# esposi-base-v1.net
KiCad netlist of a schematic drawn in EAGLE
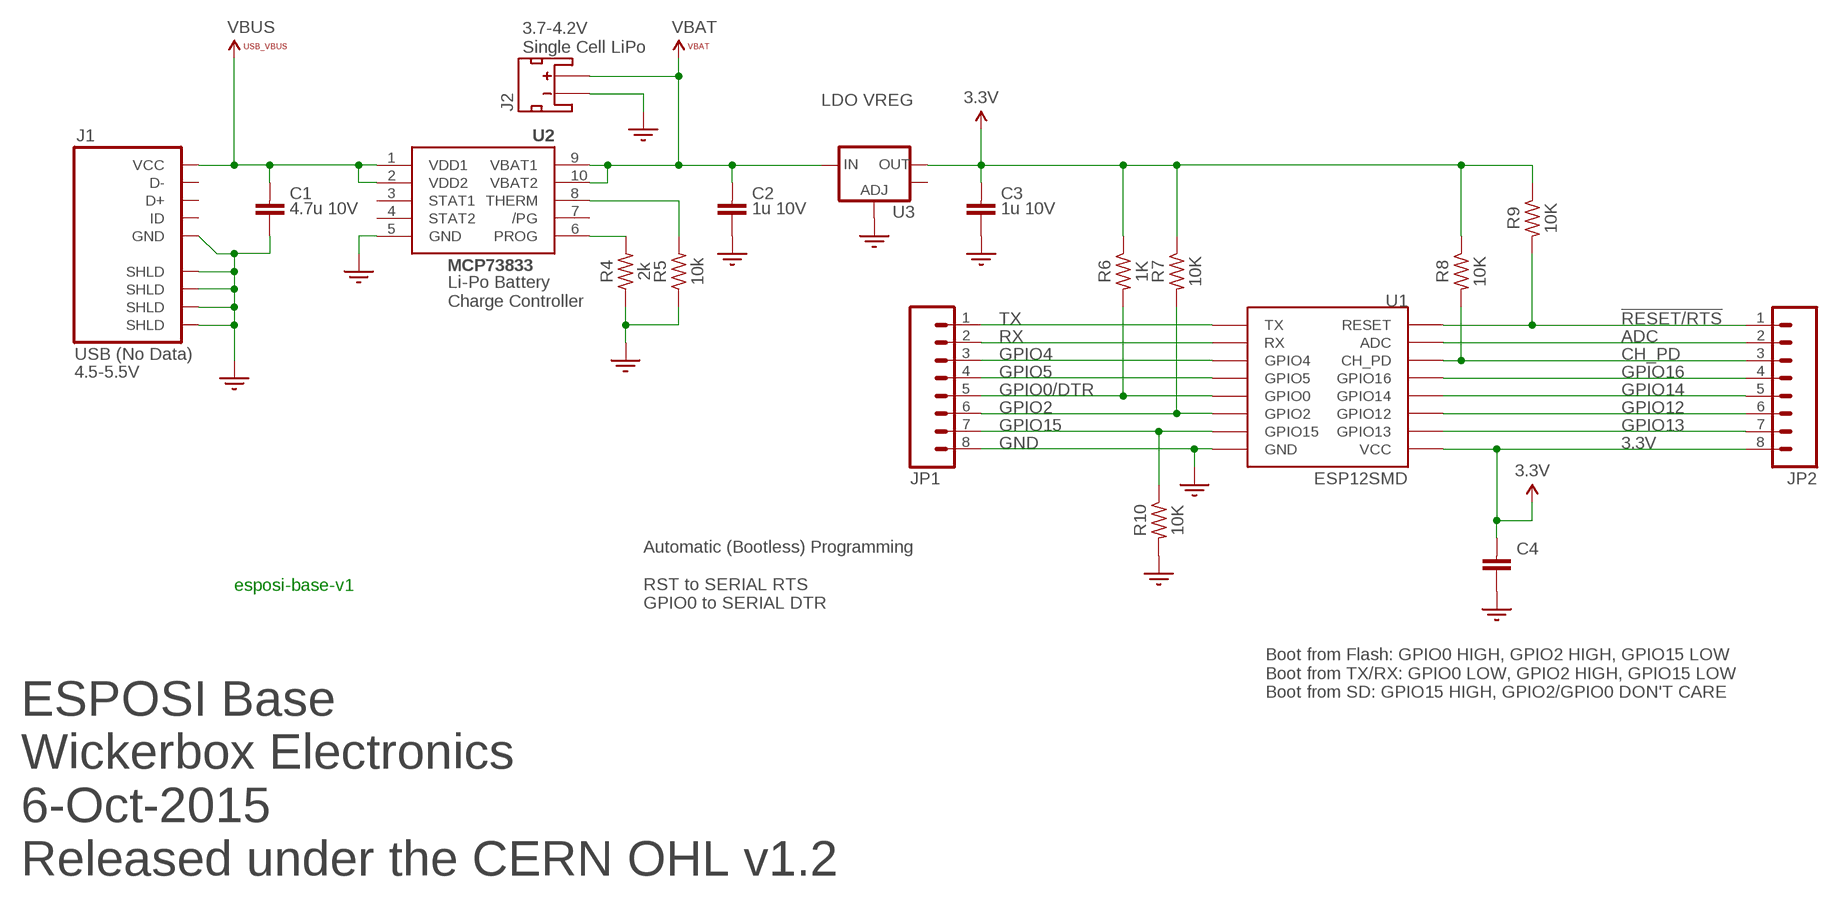
[diagram p0: schematic, sheet 1]

(export (version "E")
  (design (tool "Eeschema 10.0.6"))
  (components
    (comp (ref "C1")
      (value "4.7u 10V")
      (footprint "eagle-import:RLC-0805")
      (libsource (lib "eagle-import") (part "CAP-0805"))
    )
    (comp (ref "C2")
      (value "1u 10V")
      (footprint "eagle-import:RLC-0603")
      (libsource (lib "eagle-import") (part "CAP-0603"))
    )
    (comp (ref "C3")
      (value "1u 10V")
      (footprint "eagle-import:RLC-0603")
      (libsource (lib "eagle-import") (part "CAP-0603"))
    )
    (comp (ref "C4")
      (value "CAP-0402")
      (footprint "eagle-import:RLC-0402")
      (libsource (lib "eagle-import") (part "CAP-0402"))
    )
    (comp (ref "J1")
      (value "USB (No Data)")
      (footprint "eagle-import:ZX62D-B-5P8")
      (libsource (lib "eagle-import") (part "ZX62D-B-5P8"))
    )
    (comp (ref "J2")
      (value "JST_2MM_MALE")
      (footprint "eagle-import:JST-2-SMD")
      (libsource (lib "eagle-import") (part "JST_2MM_MALE"))
    )
    (comp (ref "JP1")
      (value "M08NO_SILK_FEMALE_PTH")
      (footprint "eagle-import:1X08_NO_SILK")
      (libsource (lib "eagle-import") (part "M08NO_SILK_FEMALE_PTH"))
    )
    (comp (ref "JP2")
      (value "M08NO_SILK_FEMALE_PTH")
      (footprint "eagle-import:1X08_NO_SILK")
      (libsource (lib "eagle-import") (part "M08NO_SILK_FEMALE_PTH"))
    )
    (comp (ref "R4")
      (value "2k")
      (footprint "eagle-import:RLC-0402")
      (libsource (lib "eagle-import") (part "RES-0402"))
    )
    (comp (ref "R5")
      (value "10k")
      (footprint "eagle-import:RLC-0402")
      (libsource (lib "eagle-import") (part "RES-0402"))
    )
    (comp (ref "R6")
      (value "1K")
      (footprint "eagle-import:RLC-0402")
      (libsource (lib "eagle-import") (part "RES-0402"))
    )
    (comp (ref "R7")
      (value "10K")
      (footprint "eagle-import:RLC-0402")
      (libsource (lib "eagle-import") (part "RES-0402"))
    )
    (comp (ref "R8")
      (value "10K")
      (footprint "eagle-import:RLC-0402")
      (libsource (lib "eagle-import") (part "RES-0402"))
    )
    (comp (ref "R9")
      (value "10K")
      (footprint "eagle-import:RLC-0402")
      (libsource (lib "eagle-import") (part "RES-0402"))
    )
    (comp (ref "R10")
      (value "10K")
      (footprint "eagle-import:RLC-0402")
      (libsource (lib "eagle-import") (part "RES-0402"))
    )
    (comp (ref "U1")
      (value "ESP12SMD")
      (footprint "eagle-import:ESP12_SMD")
      (libsource (lib "eagle-import") (part "ESP12SMD"))
    )
    (comp (ref "U2")
      (value "MCP73833-UN")
      (footprint "eagle-import:MSOP10")
      (libsource (lib "eagle-import") (part "MCP73833-UN"))
    )
    (comp (ref "U3")
      (value "V_REG_LM1117SOT223")
      (footprint "eagle-import:SOT223")
      (libsource (lib "eagle-import") (part "V_REG_LM1117SOT223"))
    )
  )
  (nets
    (net (code "1") (name "/ADC") (class "Default")
      (node (ref "JP2") (pin "2") (pinfunction "2_2") (pintype "passive"))
      (node (ref "U1") (pin "ADC") (pinfunction "ADC_ADC") (pintype "bidirectional"))
    )
    (net (code "2") (name "/CH_PD") (class "Default")
      (node (ref "JP2") (pin "3") (pinfunction "3_3") (pintype "passive"))
      (node (ref "R8") (pin "2") (pinfunction "2_2") (pintype "passive"))
      (node (ref "U1") (pin "CH_PD") (pinfunction "CH_PD_CH_PD") (pintype "bidirectional"))
    )
    (net (code "3") (name "/GPIO0{slash}DTR") (class "Default")
      (node (ref "JP1") (pin "5") (pinfunction "5_5") (pintype "passive"))
      (node (ref "R6") (pin "2") (pinfunction "2_2") (pintype "passive"))
      (node (ref "U1") (pin "GPIO0") (pinfunction "GPIO0_GPIO0") (pintype "bidirectional"))
    )
    (net (code "4") (name "/GPIO2") (class "Default")
      (node (ref "JP1") (pin "6") (pinfunction "6_6") (pintype "passive"))
      (node (ref "R7") (pin "2") (pinfunction "2_2") (pintype "passive"))
      (node (ref "U1") (pin "GPIO2") (pinfunction "GPIO2_GPIO2") (pintype "bidirectional"))
    )
    (net (code "5") (name "/GPIO4") (class "Default")
      (node (ref "JP1") (pin "3") (pinfunction "3_3") (pintype "passive"))
      (node (ref "U1") (pin "GPIO4") (pinfunction "GPIO4_GPIO4") (pintype "bidirectional"))
    )
    (net (code "6") (name "/GPIO5") (class "Default")
      (node (ref "JP1") (pin "4") (pinfunction "4_4") (pintype "passive"))
      (node (ref "U1") (pin "GPIO5") (pinfunction "GPIO5_GPIO5") (pintype "bidirectional"))
    )
    (net (code "7") (name "/GPIO12") (class "Default")
      (node (ref "JP2") (pin "6") (pinfunction "6_6") (pintype "passive"))
      (node (ref "U1") (pin "GPIO12") (pinfunction "GPIO12_GPIO12") (pintype "bidirectional"))
    )
    (net (code "8") (name "/GPIO13") (class "Default")
      (node (ref "JP2") (pin "7") (pinfunction "7_7") (pintype "passive"))
      (node (ref "U1") (pin "GPIO13") (pinfunction "GPIO13_GPIO13") (pintype "bidirectional"))
    )
    (net (code "9") (name "/GPIO14") (class "Default")
      (node (ref "JP2") (pin "5") (pinfunction "5_5") (pintype "passive"))
      (node (ref "U1") (pin "GPIO14") (pinfunction "GPIO14_GPIO14") (pintype "bidirectional"))
    )
    (net (code "10") (name "/GPIO15") (class "Default")
      (node (ref "JP1") (pin "7") (pinfunction "7_7") (pintype "passive"))
      (node (ref "R10") (pin "1") (pinfunction "1_1") (pintype "passive"))
      (node (ref "U1") (pin "GPIO15") (pinfunction "GPIO15_GPIO15") (pintype "bidirectional"))
    )
    (net (code "11") (name "/GPIO16") (class "Default")
      (node (ref "JP2") (pin "4") (pinfunction "4_4") (pintype "passive"))
      (node (ref "U1") (pin "GPIO16") (pinfunction "GPIO16_GPIO16") (pintype "bidirectional"))
    )
    (net (code "12") (name "/RX") (class "Default")
      (node (ref "JP1") (pin "2") (pinfunction "2_2") (pintype "passive"))
      (node (ref "U1") (pin "RX") (pinfunction "RX_RX") (pintype "bidirectional"))
    )
    (net (code "13") (name "/TX") (class "Default")
      (node (ref "JP1") (pin "1") (pinfunction "1_1") (pintype "passive"))
      (node (ref "U1") (pin "TX") (pinfunction "TX_TX") (pintype "bidirectional"))
    )
    (net (code "14") (name "/~{RESET{slash}RTS}") (class "Default")
      (node (ref "JP2") (pin "1") (pinfunction "1_1") (pintype "passive"))
      (node (ref "R9") (pin "2") (pinfunction "2_2") (pintype "passive"))
      (node (ref "U1") (pin "RESET") (pinfunction "RESET_RESET") (pintype "bidirectional"))
    )
    (net (code "15") (name "3.3V") (class "Default")
      (node (ref "C3") (pin "2") (pinfunction "1_2") (pintype "passive"))
      (node (ref "C4") (pin "1") (pinfunction "1_1") (pintype "passive"))
      (node (ref "JP2") (pin "8") (pinfunction "8_8") (pintype "passive"))
      (node (ref "R6") (pin "1") (pinfunction "1_1") (pintype "passive"))
      (node (ref "R7") (pin "1") (pinfunction "1_1") (pintype "passive"))
      (node (ref "R8") (pin "1") (pinfunction "1_1") (pintype "passive"))
      (node (ref "R9") (pin "1") (pinfunction "1_1") (pintype "passive"))
      (node (ref "U1") (pin "VCC") (pinfunction "VCC_VCC") (pintype "bidirectional"))
      (node (ref "U3") (pin "2") (pinfunction "OUT_2") (pintype "output"))
    )
    (net (code "16") (name "GND") (class "Default")
      (node (ref "C1") (pin "2") (pinfunction "2_2") (pintype "passive"))
      (node (ref "C2") (pin "1") (pinfunction "2_1") (pintype "passive"))
      (node (ref "C3") (pin "1") (pinfunction "2_1") (pintype "passive"))
      (node (ref "C4") (pin "2") (pinfunction "2_2") (pintype "passive"))
      (node (ref "J1") (pin "P$1") (pinfunction "SHLD_P$1") (pintype "power_in"))
      (node (ref "J1") (pin "P$2") (pinfunction "SHLD_P$2") (pintype "power_in"))
      (node (ref "J1") (pin "P$3") (pinfunction "SHLD_P$3") (pintype "power_in"))
      (node (ref "J1") (pin "P$4") (pinfunction "SHLD_P$4") (pintype "power_in"))
      (node (ref "J1") (pin "P5") (pinfunction "GND_P5") (pintype "power_in"))
      (node (ref "J2") (pin "1") (pinfunction "-_1") (pintype "bidirectional"))
      (node (ref "JP1") (pin "8") (pinfunction "8_8") (pintype "passive"))
      (node (ref "R10") (pin "2") (pinfunction "2_2") (pintype "passive"))
      (node (ref "R4") (pin "1") (pinfunction "1_1") (pintype "passive"))
      (node (ref "R5") (pin "1") (pinfunction "1_1") (pintype "passive"))
      (node (ref "U1") (pin "GND") (pinfunction "GND_GND") (pintype "bidirectional"))
      (node (ref "U2") (pin "5") (pinfunction "GND_5") (pintype "power_in"))
      (node (ref "U3") (pin "1") (pinfunction "ADJ_1") (pintype "input"))
    )
    (net (code "17") (name "Net-(U2-PROG)") (class "Default")
      (node (ref "R4") (pin "2") (pinfunction "2_2") (pintype "passive"))
      (node (ref "U2") (pin "6") (pinfunction "PROG_6") (pintype "input"))
    )
    (net (code "18") (name "Net-(U2-THERM)") (class "Default")
      (node (ref "R5") (pin "2") (pinfunction "2_2") (pintype "passive"))
      (node (ref "U2") (pin "8") (pinfunction "THERM_8") (pintype "bidirectional"))
    )
    (net (code "19") (name "VBAT") (class "Default")
      (node (ref "C2") (pin "2") (pinfunction "1_2") (pintype "passive"))
      (node (ref "J2") (pin "2") (pinfunction "+_2") (pintype "bidirectional"))
      (node (ref "U2") (pin "10") (pinfunction "VBAT2_10") (pintype "output"))
      (node (ref "U2") (pin "9") (pinfunction "VBAT1_9") (pintype "output"))
      (node (ref "U3") (pin "3") (pinfunction "IN_3") (pintype "input"))
    )
    (net (code "20") (name "VBUS") (class "Default")
      (node (ref "C1") (pin "1") (pinfunction "1_1") (pintype "passive"))
      (node (ref "J1") (pin "P1") (pinfunction "VCC_P1") (pintype "power_in"))
      (node (ref "U2") (pin "1") (pinfunction "VDD1_1") (pintype "power_in"))
      (node (ref "U2") (pin "2") (pinfunction "VDD2_2") (pintype "power_in"))
    )
    (net (code "21") (name "unconnected-(J1-D+-PadP3)") (class "Default")
      (node (ref "J1") (pin "P3") (pinfunction "D+_P3") (pintype "bidirectional"))
    )
    (net (code "22") (name "unconnected-(J1-D--PadP2)") (class "Default")
      (node (ref "J1") (pin "P2") (pinfunction "D-_P2") (pintype "bidirectional"))
    )
    (net (code "23") (name "unconnected-(J1-ID-PadP4)") (class "Default")
      (node (ref "J1") (pin "P4") (pinfunction "ID_P4") (pintype "bidirectional"))
    )
    (net (code "24") (name "unconnected-(J2-PAD1-PadNC1)") (class "Default")
      (node (ref "J2") (pin "NC1") (pinfunction "PAD1_NC1") (pintype "bidirectional"))
    )
    (net (code "25") (name "unconnected-(J2-PAD2-PadNC2)") (class "Default")
      (node (ref "J2") (pin "NC2") (pinfunction "PAD2_NC2") (pintype "bidirectional"))
    )
    (net (code "26") (name "unconnected-(U2-STAT1-Pad3)") (class "Default")
      (node (ref "U2") (pin "3") (pinfunction "STAT1_3") (pintype "passive"))
    )
    (net (code "27") (name "unconnected-(U2-STAT2-Pad4)") (class "Default")
      (node (ref "U2") (pin "4") (pinfunction "STAT2_4") (pintype "passive"))
    )
    (net (code "28") (name "unconnected-(U2-{slash}PG-Pad7)") (class "Default")
      (node (ref "U2") (pin "7") (pinfunction "/PG_7") (pintype "passive"))
    )
    (net (code "29") (name "unconnected-(U3-OUT-Pad4)") (class "Default")
      (node (ref "U3") (pin "4") (pinfunction "OUT_4") (pintype "output"))
    )
  )
)
